# BPM_RULE_COMPLIANT_itr1_ver1.net
KiCad netlist of a schematic drawn in EAGLE
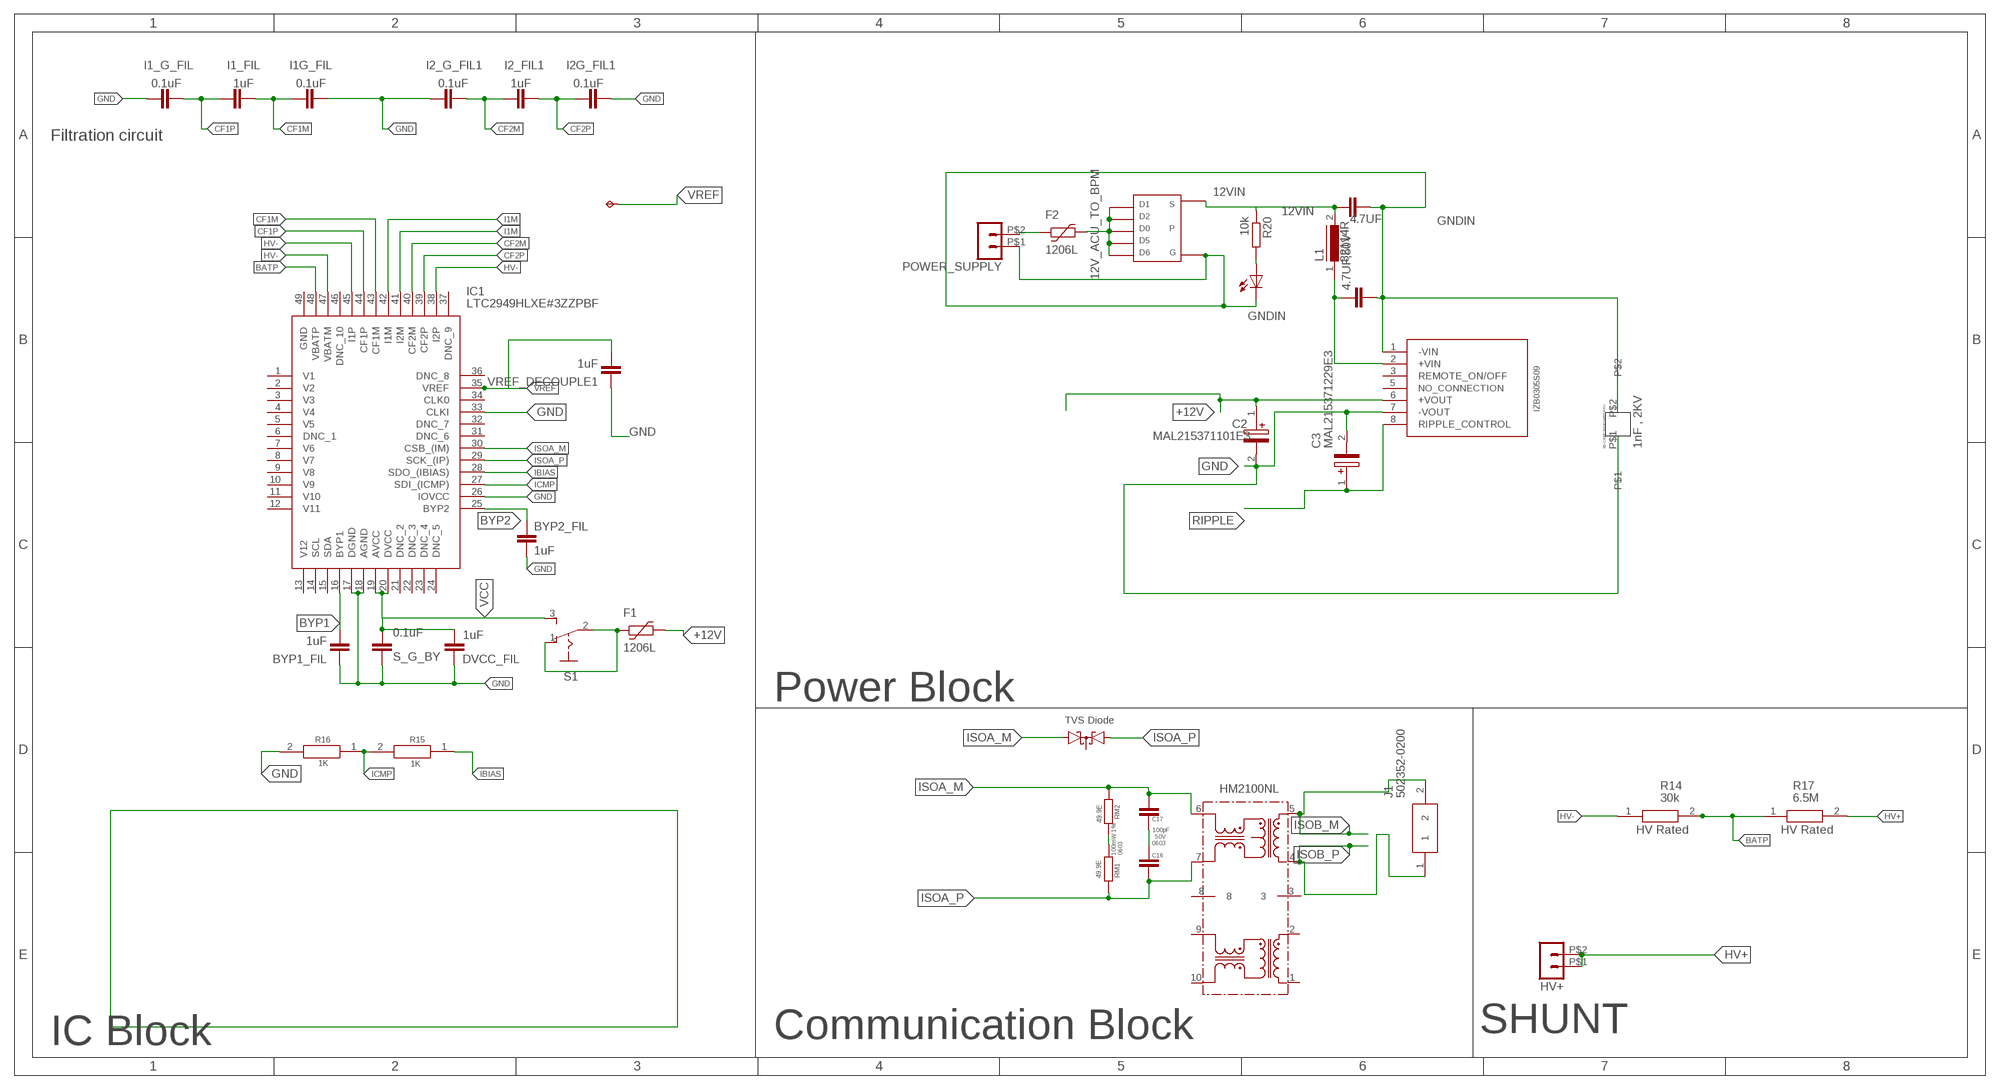
[diagram p0: schematic, sheet 1]

(export (version "E")
  (design (tool "Eeschema 10.0.6"))
  (components
    (comp (ref "4.7UF")
      (value "C-EUC1206")
      (footprint "eagle-import:C1206")
      (libsource (lib "eagle-import") (part "C-EUC1206"))
    )
    (comp (ref "4.7UF,50V")
      (value "C-EUC1206")
      (footprint "eagle-import:C1206")
      (libsource (lib "eagle-import") (part "C-EUC1206"))
    )
    (comp (ref "BYP1_FIL")
      (value "1uF")
      (footprint "eagle-import:C0603")
      (libsource (lib "eagle-import") (part "rcl_334_C-EUC0603"))
    )
    (comp (ref "BYP2_FIL")
      (value "1uF")
      (footprint "eagle-import:C0603")
      (libsource (lib "eagle-import") (part "rcl_334_C-EUC0603"))
    )
    (comp (ref "C2")
      (value "MAL215371101E3")
      (footprint "eagle-import:CAPAE1060X1060N")
      (fields (field (name "MOUSER_PART_NUMBER") "594-MAL215371101E3"))
      (libsource (lib "eagle-import") (part "MAL215371101E3"))
    )
    (comp (ref "C3")
      (value "MAL215371229E3")
      (footprint "eagle-import:CAPAE860X680N")
      (fields (field (name "MOUSER_PART_NUMBER") "594-MAL215371229E3"))
      (libsource (lib "eagle-import") (part "MAL215371229E3"))
    )
    (comp (ref "C15")
      (value "TPPAD1-13")
      (footprint "eagle-import:P1-13")
      (libsource (lib "eagle-import") (part "TPPAD1-13"))
    )
    (comp (ref "C16")
      (value "100pF")
      (footprint "eagle-import:C0603")
      (libsource (lib "eagle-import") (part "resistor_348_C-EUC0603"))
    )
    (comp (ref "C17")
      (value "100pF")
      (footprint "eagle-import:C0603")
      (libsource (lib "eagle-import") (part "resistor_348_C-EUC0603"))
    )
    (comp (ref "DVCC_FIL")
      (value "1uF")
      (footprint "eagle-import:C0603")
      (libsource (lib "eagle-import") (part "rcl_334_C-EUC0603"))
    )
    (comp (ref "F1")
      (value "1206L")
      (footprint "eagle-import:1206L")
      (libsource (lib "eagle-import") (part "1206L"))
    )
    (comp (ref "F2")
      (value "1206L")
      (footprint "eagle-import:1206L")
      (libsource (lib "eagle-import") (part "1206L"))
    )
    (comp (ref "HM2100NL")
      (value "HM2100NL")
      (footprint "eagle-import:HM2100NL")
      (libsource (lib "eagle-import") (part "HM2100NL"))
    )
    (comp (ref "HV+")
      (value "MOLEX2PIN43650-0200")
      (footprint "eagle-import:43650-0200")
      (libsource (lib "eagle-import") (part "MOLEX2PIN43650-0200"))
    )
    (comp (ref "I1G_FIL")
      (value "0.1uF")
      (footprint "eagle-import:C0603")
      (libsource (lib "eagle-import") (part "rcl_334_C-EUC0603"))
    )
    (comp (ref "I1_FIL")
      (value "1uF")
      (footprint "eagle-import:C0603")
      (libsource (lib "eagle-import") (part "rcl_334_C-EUC0603"))
    )
    (comp (ref "I1_G_FIL")
      (value "0.1uF")
      (footprint "eagle-import:C0603")
      (libsource (lib "eagle-import") (part "rcl_334_C-EUC0603"))
    )
    (comp (ref "I2G_FIL1")
      (value "0.1uF")
      (footprint "eagle-import:C0603")
      (libsource (lib "eagle-import") (part "rcl_334_C-EUC0603"))
    )
    (comp (ref "I2_FIL1")
      (value "1uF")
      (footprint "eagle-import:C0603")
      (libsource (lib "eagle-import") (part "rcl_334_C-EUC0603"))
    )
    (comp (ref "I2_G_FIL1")
      (value "0.1uF")
      (footprint "eagle-import:C0603")
      (libsource (lib "eagle-import") (part "rcl_334_C-EUC0603"))
    )
    (comp (ref "IC1")
      (value "LTC2949HLXE#3ZZPBF")
      (footprint "eagle-import:QFP50P900X900X160-49N")
      (fields (field (name "MOUSER_PART_NUMBER") "584-949HLXE#3ZZPBF"))
      (libsource (lib "eagle-import") (part "LTC2949HLXE#3ZZPBF"))
    )
    (comp (ref "IM1")
      (value "TVS")
      (footprint "eagle-import:SOT23")
      (libsource (lib "eagle-import") (part "BAS40-05"))
    )
    (comp (ref "J1")
      (value "502352-0200")
      (footprint "eagle-import:5023520200")
      (fields (field (name "MOUSER_PART_NUMBER") "538-502352-0200"))
      (libsource (lib "eagle-import") (part "502352-0200"))
    )
    (comp (ref "L1")
      (value "82114R")
      (footprint "eagle-import:82114R")
      (libsource (lib "eagle-import") (part "82114R"))
    )
    (comp (ref "POWER_SUPPLY")
      (value "MOLEX2PIN43045-0212")
      (footprint "eagle-import:43045-0212")
      (libsource (lib "eagle-import") (part "MOLEX2PIN43045-0212"))
    )
    (comp (ref "PWR_LED")
      (value "LED-FKIT-1206")
      (footprint "eagle-import:FKIT-LED-1206")
      (libsource (lib "eagle-import") (part "LED-FKIT-1206"))
    )
    (comp (ref "R14")
      (value "30k")
      (footprint "eagle-import:RESC3216X70N")
      (fields (field (name "MANUFACTURER_PART_NUMBER") "HV73V2BTTD6494F"))
      (libsource (lib "eagle-import") (part "HV73V2BTTD6494F"))
    )
    (comp (ref "R15")
      (value "1K")
      (footprint "eagle-import:RESC1608X50N")
      (fields
        (field (name "ARROW_PART_NUMBER") "CRCW06031K00FKEC")
        (field (name "MOUSER_PART_NUMBER") "71-CRCW06031K00FKEC")
      )
      (libsource (lib "eagle-import") (part "CRCW06031K00FKEC"))
    )
    (comp (ref "R16")
      (value "1K")
      (footprint "eagle-import:RESC1608X50N")
      (fields
        (field (name "ARROW_PART_NUMBER") "CRCW06031K00FKEC")
        (field (name "MOUSER_PART_NUMBER") "71-CRCW06031K00FKEC")
      )
      (libsource (lib "eagle-import") (part "CRCW06031K00FKEC"))
    )
    (comp (ref "R17")
      (value "6.5M")
      (footprint "eagle-import:RESC3216X70N")
      (fields (field (name "MANUFACTURER_PART_NUMBER") "HV73V2BTTD6494F"))
      (libsource (lib "eagle-import") (part "HV73V2BTTD6494F"))
    )
    (comp (ref "R20")
      (value "10k")
      (footprint "eagle-import:R0805")
      (libsource (lib "eagle-import") (part "R-EU_R0805"))
    )
    (comp (ref "RM1")
      (value "49.9E")
      (footprint "eagle-import:R0603")
      (libsource (lib "eagle-import") (part "resistor_348_R-EU_R0603"))
    )
    (comp (ref "RM2")
      (value "49.9E")
      (footprint "eagle-import:R0603")
      (libsource (lib "eagle-import") (part "resistor_348_R-EU_R0603"))
    )
    (comp (ref "S1")
      (value "STS121PC04")
      (footprint "eagle-import:STS121PC04")
      (libsource (lib "eagle-import") (part "STS121PC04"))
    )
    (comp (ref "S_G_BY")
      (value "0.1uF")
      (footprint "eagle-import:C0603")
      (libsource (lib "eagle-import") (part "rcl_334_C-EUC0603"))
    )
    (comp (ref "U$1")
      (value "BPM_CONV")
      (footprint "eagle-import:BPM_CONV")
      (libsource (lib "eagle-import") (part "BPM_CONV"))
    )
    (comp (ref "U$2")
      (value "80-C330C102KGR5TATU")
      (footprint "eagle-import:80-C330C102KGR5TATU")
      (libsource (lib "eagle-import") (part "80-C330C102KGR5TATU"))
    )
    (comp (ref "U$10")
      (value "TSOP-6_PMOS")
      (footprint "eagle-import:TSOP-6_PMOS")
      (libsource (lib "eagle-import") (part "TSOP-6_PMOS"))
    )
    (comp (ref "VREF_DECOUPLE1")
      (value "1uF")
      (footprint "eagle-import:C0603")
      (libsource (lib "eagle-import") (part "rcl_334_C-EUC0603"))
    )
  )
  (nets
    (net (code "1") (name "+12V") (class "Default")
      (node (ref "C2") (pin "1") (pinfunction "+_1") (pintype "bidirectional"))
      (node (ref "F1") (pin "P$2") (pinfunction "2_P$2") (pintype "passive"))
      (node (ref "U$1") (pin "6") (pinfunction "+VOUT_6") (pintype "bidirectional"))
    )
    (net (code "2") (name "/12VIN") (class "Default")
      (node (ref "4.7UF") (pin "1") (pinfunction "1_1") (pintype "passive"))
      (node (ref "L1") (pin "2") (pinfunction "2_2") (pintype "passive"))
      (node (ref "R20") (pin "1") (pinfunction "1_1") (pintype "passive"))
      (node (ref "U$10") (pin "S") (pinfunction "S_S") (pintype "bidirectional"))
    )
    (net (code "3") (name "/12V_ACU_TO_BPM") (class "Default")
      (node (ref "F2") (pin "P$2") (pinfunction "2_P$2") (pintype "passive"))
      (node (ref "U$10") (pin "1") (pinfunction "1_1") (pintype "bidirectional"))
      (node (ref "U$10") (pin "2") (pinfunction "2_2") (pintype "bidirectional"))
      (node (ref "U$10") (pin "5") (pinfunction "5_5") (pintype "bidirectional"))
      (node (ref "U$10") (pin "6") (pinfunction "6_6") (pintype "bidirectional"))
      (node (ref "U$10") (pin "D") (pinfunction "D0_D") (pintype "bidirectional"))
    )
    (net (code "4") (name "/GNDIN") (class "Default")
      (node (ref "4.7UF") (pin "2") (pinfunction "2_2") (pintype "passive"))
      (node (ref "4.7UF,50V") (pin "2") (pinfunction "2_2") (pintype "passive"))
      (node (ref "POWER_SUPPLY") (pin "P$1") (pinfunction "1_P$1") (pintype "passive"))
      (node (ref "PWR_LED") (pin "C") (pinfunction "C_C") (pintype "passive"))
      (node (ref "U$1") (pin "1") (pinfunction "-VIN_1") (pintype "bidirectional"))
      (node (ref "U$10") (pin "G") (pinfunction "G_G") (pintype "bidirectional"))
      (node (ref "U$2") (pin "P$2") (pinfunction "P$2_P$2") (pintype "bidirectional"))
    )
    (net (code "5") (name "BATP") (class "Default")
      (node (ref "IC1") (pin "48") (pinfunction "VBATP_48") (pintype "bidirectional"))
      (node (ref "R14") (pin "2") (pinfunction "2_2") (pintype "bidirectional"))
      (node (ref "R17") (pin "1") (pinfunction "1_1") (pintype "bidirectional"))
    )
    (net (code "6") (name "BYP1") (class "Default")
      (node (ref "BYP1_FIL") (pin "2") (pinfunction "2_2") (pintype "passive"))
      (node (ref "IC1") (pin "16") (pinfunction "BYP1_16") (pintype "bidirectional"))
    )
    (net (code "7") (name "BYP2") (class "Default")
      (node (ref "BYP2_FIL") (pin "1") (pinfunction "1_1") (pintype "passive"))
      (node (ref "IC1") (pin "25") (pinfunction "BYP2_25") (pintype "bidirectional"))
    )
    (net (code "8") (name "CF1M") (class "Default")
      (node (ref "I1G_FIL") (pin "1") (pinfunction "1_1") (pintype "passive"))
      (node (ref "I1_FIL") (pin "1") (pinfunction "1_1") (pintype "passive"))
      (node (ref "IC1") (pin "43") (pinfunction "CF1M_43") (pintype "bidirectional"))
    )
    (net (code "9") (name "CF1P") (class "Default")
      (node (ref "I1_FIL") (pin "2") (pinfunction "2_2") (pintype "passive"))
      (node (ref "I1_G_FIL") (pin "2") (pinfunction "2_2") (pintype "passive"))
      (node (ref "IC1") (pin "44") (pinfunction "CF1P_44") (pintype "bidirectional"))
    )
    (net (code "10") (name "CF2M") (class "Default")
      (node (ref "I2_FIL1") (pin "2") (pinfunction "2_2") (pintype "passive"))
      (node (ref "I2_G_FIL1") (pin "1") (pinfunction "1_1") (pintype "passive"))
      (node (ref "IC1") (pin "40") (pinfunction "CF2M_40") (pintype "bidirectional"))
    )
    (net (code "11") (name "CF2P") (class "Default")
      (node (ref "I2G_FIL1") (pin "1") (pinfunction "1_1") (pintype "passive"))
      (node (ref "I2_FIL1") (pin "1") (pinfunction "1_1") (pintype "passive"))
      (node (ref "IC1") (pin "39") (pinfunction "CF2P_39") (pintype "bidirectional"))
    )
    (net (code "12") (name "GND") (class "Default")
      (node (ref "BYP1_FIL") (pin "1") (pinfunction "1_1") (pintype "passive"))
      (node (ref "BYP2_FIL") (pin "2") (pinfunction "2_2") (pintype "passive"))
      (node (ref "C2") (pin "2") (pinfunction "-_2") (pintype "bidirectional"))
      (node (ref "C3") (pin "2") (pinfunction "-_2") (pintype "bidirectional"))
      (node (ref "DVCC_FIL") (pin "1") (pinfunction "1_1") (pintype "passive"))
      (node (ref "I1G_FIL") (pin "2") (pinfunction "2_2") (pintype "passive"))
      (node (ref "I1_G_FIL") (pin "1") (pinfunction "1_1") (pintype "passive"))
      (node (ref "I2G_FIL1") (pin "2") (pinfunction "2_2") (pintype "passive"))
      (node (ref "I2_G_FIL1") (pin "2") (pinfunction "2_2") (pintype "passive"))
      (node (ref "IC1") (pin "17") (pinfunction "DGND_17") (pintype "bidirectional"))
      (node (ref "IC1") (pin "18") (pinfunction "AGND_18") (pintype "bidirectional"))
      (node (ref "IC1") (pin "26") (pinfunction "IOVCC_26") (pintype "bidirectional"))
      (node (ref "IC1") (pin "33") (pinfunction "CLKI_33") (pintype "bidirectional"))
      (node (ref "R16") (pin "2") (pinfunction "2_2") (pintype "bidirectional"))
      (node (ref "S_G_BY") (pin "1") (pinfunction "1_1") (pintype "passive"))
      (node (ref "U$1") (pin "7") (pinfunction "-VOUT_7") (pintype "bidirectional"))
      (node (ref "U$2") (pin "P$1") (pinfunction "P$1_P$1") (pintype "bidirectional"))
      (node (ref "VREF_DECOUPLE1") (pin "1") (pinfunction "1_1") (pintype "passive"))
    )
    (net (code "13") (name "HV+") (class "Default")
      (node (ref "HV+") (pin "P$1") (pinfunction "1_P$1") (pintype "passive"))
      (node (ref "HV+") (pin "P$2") (pinfunction "2_P$2") (pintype "passive"))
      (node (ref "R17") (pin "2") (pinfunction "2_2") (pintype "bidirectional"))
    )
    (net (code "14") (name "HV-") (class "Default")
      (node (ref "IC1") (pin "38") (pinfunction "I2P_38") (pintype "bidirectional"))
      (node (ref "IC1") (pin "45") (pinfunction "I1P_45") (pintype "bidirectional"))
      (node (ref "IC1") (pin "47") (pinfunction "VBATM_47") (pintype "bidirectional"))
      (node (ref "R14") (pin "1") (pinfunction "1_1") (pintype "bidirectional"))
    )
    (net (code "15") (name "I1M") (class "Default")
      (node (ref "IC1") (pin "41") (pinfunction "I2M_41") (pintype "bidirectional"))
      (node (ref "IC1") (pin "42") (pinfunction "I1M_42") (pintype "bidirectional"))
    )
    (net (code "16") (name "IBIAS") (class "Default")
      (node (ref "IC1") (pin "28") (pinfunction "SDO_(IBIAS)_28") (pintype "bidirectional"))
      (node (ref "R15") (pin "1") (pinfunction "1_1") (pintype "bidirectional"))
    )
    (net (code "17") (name "ICMP") (class "Default")
      (node (ref "IC1") (pin "27") (pinfunction "SDI_(ICMP)_27") (pintype "bidirectional"))
      (node (ref "R15") (pin "2") (pinfunction "2_2") (pintype "bidirectional"))
      (node (ref "R16") (pin "1") (pinfunction "1_1") (pintype "bidirectional"))
    )
    (net (code "18") (name "ISOA_M") (class "Default")
      (node (ref "C17") (pin "2") (pinfunction "2_2") (pintype "passive"))
      (node (ref "HM2100NL") (pin "6") (pinfunction "6_6") (pintype "passive"))
      (node (ref "IC1") (pin "30") (pinfunction "CSB_(IM)_30") (pintype "bidirectional"))
      (node (ref "IM1") (pin "2") (pinfunction "A2_2") (pintype "passive"))
      (node (ref "RM2") (pin "1") (pinfunction "1_1") (pintype "passive"))
    )
    (net (code "19") (name "ISOA_P") (class "Default")
      (node (ref "C16") (pin "1") (pinfunction "1_1") (pintype "passive"))
      (node (ref "HM2100NL") (pin "7") (pinfunction "7_7") (pintype "passive"))
      (node (ref "IC1") (pin "29") (pinfunction "SCK_(IP)_29") (pintype "bidirectional"))
      (node (ref "IM1") (pin "1") (pinfunction "A1_1") (pintype "passive"))
      (node (ref "RM1") (pin "2") (pinfunction "2_2") (pintype "passive"))
    )
    (net (code "20") (name "ISOB_M") (class "Default")
      (node (ref "HM2100NL") (pin "5") (pinfunction "5_5") (pintype "passive"))
      (node (ref "J1") (pin "2") (pinfunction "2_2") (pintype "bidirectional"))
    )
    (net (code "21") (name "ISOB_P") (class "Default")
      (node (ref "HM2100NL") (pin "4") (pinfunction "4_4") (pintype "passive"))
      (node (ref "J1") (pin "1") (pinfunction "1_1") (pintype "bidirectional"))
    )
    (net (code "22") (name "Net-(C16-Pad2)") (class "Default")
      (node (ref "C16") (pin "2") (pinfunction "2_2") (pintype "passive"))
      (node (ref "C17") (pin "1") (pinfunction "1_1") (pintype "passive"))
    )
    (net (code "23") (name "Net-(F1-1)") (class "Default")
      (node (ref "F1") (pin "P$1") (pinfunction "1_P$1") (pintype "passive"))
      (node (ref "S1") (pin "1") (pinfunction "O_1") (pintype "passive"))
      (node (ref "S1") (pin "2") (pinfunction "P_2") (pintype "passive"))
    )
    (net (code "24") (name "Net-(F2-1)") (class "Default")
      (node (ref "F2") (pin "P$1") (pinfunction "1_P$1") (pintype "passive"))
      (node (ref "POWER_SUPPLY") (pin "P$2") (pinfunction "2_P$2") (pintype "passive"))
    )
    (net (code "25") (name "Net-(PWR_LED-PadA)") (class "Default")
      (node (ref "PWR_LED") (pin "A") (pinfunction "A_A") (pintype "passive"))
      (node (ref "R20") (pin "2") (pinfunction "2_2") (pintype "passive"))
    )
    (net (code "26") (name "Net-(RM1-Pad1)") (class "Default")
      (node (ref "RM1") (pin "1") (pinfunction "1_1") (pintype "passive"))
      (node (ref "RM2") (pin "2") (pinfunction "2_2") (pintype "passive"))
    )
    (net (code "27") (name "Net-(U$1-+VIN)") (class "Default")
      (node (ref "4.7UF,50V") (pin "1") (pinfunction "1_1") (pintype "passive"))
      (node (ref "L1") (pin "1") (pinfunction "1_1") (pintype "passive"))
      (node (ref "U$1") (pin "2") (pinfunction "+VIN_2") (pintype "bidirectional"))
    )
    (net (code "28") (name "RIPPLE") (class "Default")
      (node (ref "C3") (pin "1") (pinfunction "+_1") (pintype "bidirectional"))
      (node (ref "U$1") (pin "8") (pinfunction "RIPPLE_CONTROL_8") (pintype "bidirectional"))
    )
    (net (code "29") (name "VCC") (class "Default")
      (node (ref "DVCC_FIL") (pin "2") (pinfunction "2_2") (pintype "passive"))
      (node (ref "IC1") (pin "19") (pinfunction "AVCC_19") (pintype "bidirectional"))
      (node (ref "IC1") (pin "20") (pinfunction "DVCC_20") (pintype "bidirectional"))
      (node (ref "S1") (pin "3") (pinfunction "S_3") (pintype "passive"))
      (node (ref "S_G_BY") (pin "2") (pinfunction "2_2") (pintype "passive"))
    )
    (net (code "30") (name "VREF") (class "Default")
      (node (ref "C15") (pin "TP") (pinfunction "TP_TP") (pintype "input"))
      (node (ref "IC1") (pin "35") (pinfunction "VREF_35") (pintype "bidirectional"))
      (node (ref "VREF_DECOUPLE1") (pin "2") (pinfunction "2_2") (pintype "passive"))
    )
    (net (code "31") (name "unconnected-(HM2100NL-Pad1)") (class "Default")
      (node (ref "HM2100NL") (pin "1") (pinfunction "1_1") (pintype "passive"))
    )
    (net (code "32") (name "unconnected-(HM2100NL-Pad2)") (class "Default")
      (node (ref "HM2100NL") (pin "2") (pinfunction "2_2") (pintype "passive"))
    )
    (net (code "33") (name "unconnected-(HM2100NL-Pad3)") (class "Default")
      (node (ref "HM2100NL") (pin "3") (pinfunction "3_3") (pintype "bidirectional"))
    )
    (net (code "34") (name "unconnected-(HM2100NL-Pad8)") (class "Default")
      (node (ref "HM2100NL") (pin "8") (pinfunction "8_8") (pintype "bidirectional"))
    )
    (net (code "35") (name "unconnected-(HM2100NL-Pad9)") (class "Default")
      (node (ref "HM2100NL") (pin "9") (pinfunction "9_9") (pintype "passive"))
    )
    (net (code "36") (name "unconnected-(HM2100NL-Pad10)") (class "Default")
      (node (ref "HM2100NL") (pin "10") (pinfunction "10_10") (pintype "passive"))
    )
    (net (code "37") (name "unconnected-(IC1-CLK0-Pad34)") (class "Default")
      (node (ref "IC1") (pin "34") (pinfunction "CLK0_34") (pintype "bidirectional"))
    )
    (net (code "38") (name "unconnected-(IC1-DNC_1-Pad6)") (class "Default")
      (node (ref "IC1") (pin "6") (pinfunction "DNC_1_6") (pintype "bidirectional"))
    )
    (net (code "39") (name "unconnected-(IC1-DNC_2-Pad21)") (class "Default")
      (node (ref "IC1") (pin "21") (pinfunction "DNC_2_21") (pintype "bidirectional"))
    )
    (net (code "40") (name "unconnected-(IC1-DNC_3-Pad22)") (class "Default")
      (node (ref "IC1") (pin "22") (pinfunction "DNC_3_22") (pintype "bidirectional"))
    )
    (net (code "41") (name "unconnected-(IC1-DNC_4-Pad23)") (class "Default")
      (node (ref "IC1") (pin "23") (pinfunction "DNC_4_23") (pintype "bidirectional"))
    )
    (net (code "42") (name "unconnected-(IC1-DNC_5-Pad24)") (class "Default")
      (node (ref "IC1") (pin "24") (pinfunction "DNC_5_24") (pintype "bidirectional"))
    )
    (net (code "43") (name "unconnected-(IC1-DNC_6-Pad31)") (class "Default")
      (node (ref "IC1") (pin "31") (pinfunction "DNC_6_31") (pintype "bidirectional"))
    )
    (net (code "44") (name "unconnected-(IC1-DNC_7-Pad32)") (class "Default")
      (node (ref "IC1") (pin "32") (pinfunction "DNC_7_32") (pintype "bidirectional"))
    )
    (net (code "45") (name "unconnected-(IC1-DNC_8-Pad36)") (class "Default")
      (node (ref "IC1") (pin "36") (pinfunction "DNC_8_36") (pintype "bidirectional"))
    )
    (net (code "46") (name "unconnected-(IC1-DNC_9-Pad37)") (class "Default")
      (node (ref "IC1") (pin "37") (pinfunction "DNC_9_37") (pintype "bidirectional"))
    )
    (net (code "47") (name "unconnected-(IC1-DNC_10-Pad46)") (class "Default")
      (node (ref "IC1") (pin "46") (pinfunction "DNC_10_46") (pintype "bidirectional"))
    )
    (net (code "48") (name "unconnected-(IC1-GND-Pad49)") (class "Default")
      (node (ref "IC1") (pin "49") (pinfunction "GND_49") (pintype "bidirectional"))
    )
    (net (code "49") (name "unconnected-(IC1-SCL-Pad14)") (class "Default")
      (node (ref "IC1") (pin "14") (pinfunction "SCL_14") (pintype "bidirectional"))
    )
    (net (code "50") (name "unconnected-(IC1-SDA-Pad15)") (class "Default")
      (node (ref "IC1") (pin "15") (pinfunction "SDA_15") (pintype "bidirectional"))
    )
    (net (code "51") (name "unconnected-(IC1-V1-Pad1)") (class "Default")
      (node (ref "IC1") (pin "1") (pinfunction "V1_1") (pintype "bidirectional"))
    )
    (net (code "52") (name "unconnected-(IC1-V2-Pad2)") (class "Default")
      (node (ref "IC1") (pin "2") (pinfunction "V2_2") (pintype "bidirectional"))
    )
    (net (code "53") (name "unconnected-(IC1-V3-Pad3)") (class "Default")
      (node (ref "IC1") (pin "3") (pinfunction "V3_3") (pintype "bidirectional"))
    )
    (net (code "54") (name "unconnected-(IC1-V4-Pad4)") (class "Default")
      (node (ref "IC1") (pin "4") (pinfunction "V4_4") (pintype "bidirectional"))
    )
    (net (code "55") (name "unconnected-(IC1-V5-Pad5)") (class "Default")
      (node (ref "IC1") (pin "5") (pinfunction "V5_5") (pintype "bidirectional"))
    )
    (net (code "56") (name "unconnected-(IC1-V6-Pad7)") (class "Default")
      (node (ref "IC1") (pin "7") (pinfunction "V6_7") (pintype "bidirectional"))
    )
    (net (code "57") (name "unconnected-(IC1-V7-Pad8)") (class "Default")
      (node (ref "IC1") (pin "8") (pinfunction "V7_8") (pintype "bidirectional"))
    )
    (net (code "58") (name "unconnected-(IC1-V8-Pad9)") (class "Default")
      (node (ref "IC1") (pin "9") (pinfunction "V8_9") (pintype "bidirectional"))
    )
    (net (code "59") (name "unconnected-(IC1-V9-Pad10)") (class "Default")
      (node (ref "IC1") (pin "10") (pinfunction "V9_10") (pintype "bidirectional"))
    )
    (net (code "60") (name "unconnected-(IC1-V10-Pad11)") (class "Default")
      (node (ref "IC1") (pin "11") (pinfunction "V10_11") (pintype "bidirectional"))
    )
    (net (code "61") (name "unconnected-(IC1-V11-Pad12)") (class "Default")
      (node (ref "IC1") (pin "12") (pinfunction "V11_12") (pintype "bidirectional"))
    )
    (net (code "62") (name "unconnected-(IC1-V12-Pad13)") (class "Default")
      (node (ref "IC1") (pin "13") (pinfunction "V12_13") (pintype "bidirectional"))
    )
    (net (code "63") (name "unconnected-(IM1-C-Pad3)") (class "Default")
      (node (ref "IM1") (pin "3") (pinfunction "C_3") (pintype "passive"))
    )
    (net (code "64") (name "unconnected-(U$1-REMOTE_ON{slash}OFF-Pad3)") (class "Default")
      (node (ref "U$1") (pin "3") (pinfunction "REMOTE_ON/OFF_3") (pintype "bidirectional"))
    )
  )
)
